# optodist_1_2_TH.net
KiCad netlist of a schematic drawn in EAGLE
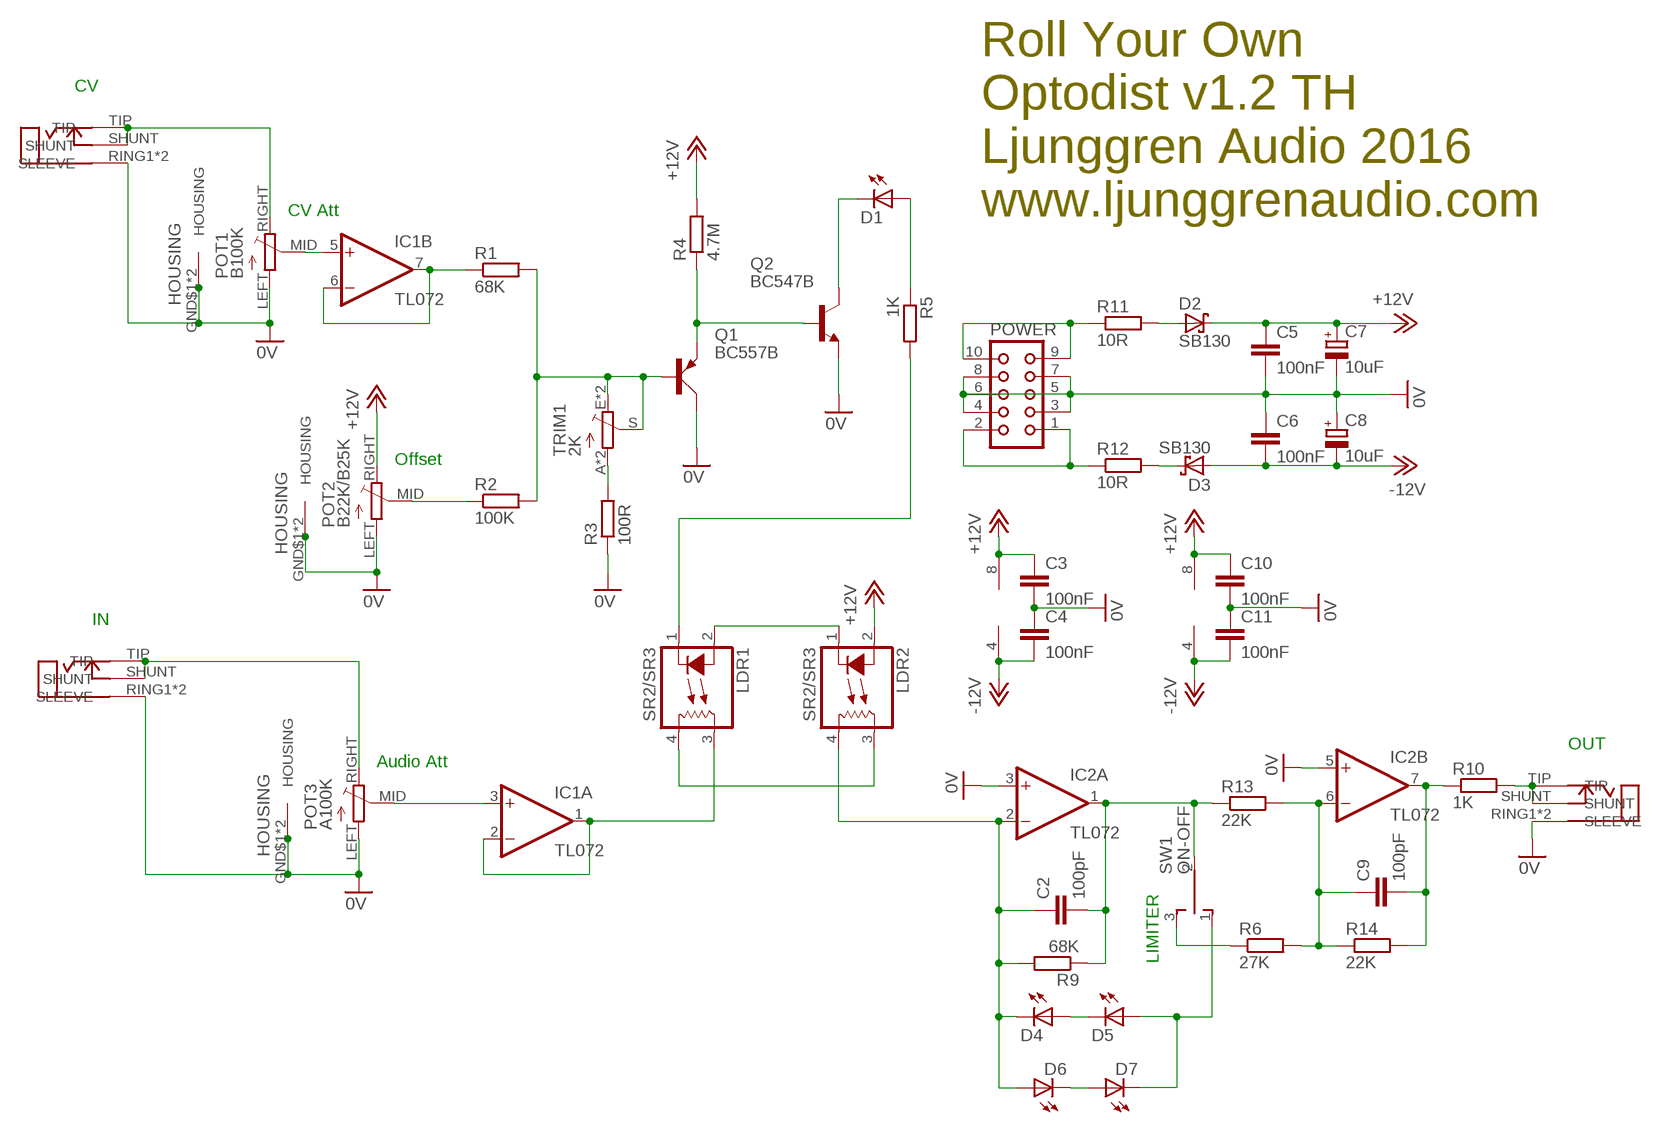
[diagram p0: schematic, sheet 1]

(export (version "E")
  (design (tool "Eeschema 10.0.6"))
  (components
    (comp (ref "C2")
      (value "100pF")
      (footprint "eagle-import:C025-024X044")
      (libsource (lib "eagle-import") (part "C-EU025-024X044"))
    )
    (comp (ref "C3")
      (value "100nF")
      (footprint "eagle-import:C025-024X044")
      (libsource (lib "eagle-import") (part "C-EU025-024X044"))
    )
    (comp (ref "C4")
      (value "100nF")
      (footprint "eagle-import:C025-024X044")
      (libsource (lib "eagle-import") (part "C-EU025-024X044"))
    )
    (comp (ref "C5")
      (value "100nF")
      (footprint "eagle-import:C025-024X044")
      (libsource (lib "eagle-import") (part "C-EU025-024X044"))
    )
    (comp (ref "C6")
      (value "100nF")
      (footprint "eagle-import:C025-024X044")
      (libsource (lib "eagle-import") (part "C-EU025-024X044"))
    )
    (comp (ref "C7")
      (value "10uF")
      (footprint "eagle-import:E2-5")
      (libsource (lib "eagle-import") (part "CPOL-EUE2-5"))
    )
    (comp (ref "C8")
      (value "10uF")
      (footprint "eagle-import:E2-5")
      (libsource (lib "eagle-import") (part "CPOL-EUE2-5"))
    )
    (comp (ref "C9")
      (value "100pF")
      (footprint "eagle-import:C025-024X044")
      (libsource (lib "eagle-import") (part "C-EU025-024X044"))
    )
    (comp (ref "C10")
      (value "100nF")
      (footprint "eagle-import:C025-024X044")
      (libsource (lib "eagle-import") (part "C-EU025-024X044"))
    )
    (comp (ref "C11")
      (value "100nF")
      (footprint "eagle-import:C025-024X044")
      (libsource (lib "eagle-import") (part "C-EU025-024X044"))
    )
    (comp (ref "CV")
      (value "ERTHENVAR_3.5MM_JACKHOLES")
      (footprint "eagle-import:ERTHENVAR")
      (libsource (lib "eagle-import") (part "ERTHENVAR_3.5MM_JACKHOLES"))
    )
    (comp (ref "D1")
      (value "LED3MM")
      (footprint "eagle-import:LED3MM")
      (libsource (lib "eagle-import") (part "LED3MM"))
    )
    (comp (ref "D2")
      (value "SB130")
      (footprint "eagle-import:DO41-7")
      (libsource (lib "eagle-import") (part "SB130DO-204AL"))
    )
    (comp (ref "D3")
      (value "SB130")
      (footprint "eagle-import:DO41-7")
      (libsource (lib "eagle-import") (part "SB130DO-204AL"))
    )
    (comp (ref "D4")
      (value "LED3MM")
      (footprint "eagle-import:LED3MM")
      (libsource (lib "eagle-import") (part "LED3MM"))
    )
    (comp (ref "D5")
      (value "LED3MM")
      (footprint "eagle-import:LED3MM")
      (libsource (lib "eagle-import") (part "LED3MM"))
    )
    (comp (ref "D6")
      (value "LED3MM")
      (footprint "eagle-import:LED3MM")
      (libsource (lib "eagle-import") (part "LED3MM"))
    )
    (comp (ref "D7")
      (value "LED3MM")
      (footprint "eagle-import:LED3MM")
      (libsource (lib "eagle-import") (part "LED3MM"))
    )
    (comp (ref "IC1")
      (value "TL072")
      (footprint "eagle-import:DIL08")
      (libsource (lib "eagle-import") (part "TL072P"))
    )
    (comp (ref "IC2")
      (value "TL072")
      (footprint "eagle-import:DIL08")
      (libsource (lib "eagle-import") (part "TL072P"))
    )
    (comp (ref "IN")
      (value "ERTHENVAR_3.5MM_JACKHOLES")
      (footprint "eagle-import:ERTHENVAR")
      (libsource (lib "eagle-import") (part "ERTHENVAR_3.5MM_JACKHOLES"))
    )
    (comp (ref "LDR1")
      (value "SR2/SR3")
      (footprint "eagle-import:VTL5C")
      (fields (field (name "MF") "VACTEC PHOTO") (field (name "MPN") "VTL5C9"))
      (libsource (lib "eagle-import") (part "VTL5CSILONEX9"))
    )
    (comp (ref "LDR2")
      (value "SR2/SR3")
      (footprint "eagle-import:VTL5C")
      (fields (field (name "MF") "VACTEC PHOTO") (field (name "MPN") "VTL5C9"))
      (libsource (lib "eagle-import") (part "VTL5CSILONEX9"))
    )
    (comp (ref "OUT")
      (value "ERTHENVAR_3.5MM_JACKHOLES")
      (footprint "eagle-import:ERTHENVAR")
      (libsource (lib "eagle-import") (part "ERTHENVAR_3.5MM_JACKHOLES"))
    )
    (comp (ref "POT1")
      (value "B100K")
      (footprint "eagle-import:POT-ALPHA9")
      (libsource (lib "eagle-import") (part "POT-ALPHA9"))
    )
    (comp (ref "POT2")
      (value "B22K/B25K")
      (footprint "eagle-import:POT-ALPHA9")
      (libsource (lib "eagle-import") (part "POT-ALPHA9"))
    )
    (comp (ref "POT3")
      (value "A100K")
      (footprint "eagle-import:POT-ALPHA9")
      (libsource (lib "eagle-import") (part "POT-ALPHA9"))
    )
    (comp (ref "POWER")
      (value "CON10L")
      (footprint "eagle-import:CON10L")
      (libsource (lib "eagle-import") (part "CON10L"))
    )
    (comp (ref "Q1")
      (value "BC557B")
      (footprint "eagle-import:TO92-LINE")
      (libsource (lib "eagle-import") (part "BC557TO92-LINE"))
    )
    (comp (ref "Q2")
      (value "BC547B")
      (footprint "eagle-import:TO92-LINE")
      (libsource (lib "eagle-import") (part "BC547TO92-LINE"))
    )
    (comp (ref "R1")
      (value "68K")
      (footprint "eagle-import:0207_9")
      (libsource (lib "eagle-import") (part "R-EU_0207/10"))
    )
    (comp (ref "R2")
      (value "100K")
      (footprint "eagle-import:0207_9")
      (libsource (lib "eagle-import") (part "R-EU_0207/10"))
    )
    (comp (ref "R3")
      (value "100R")
      (footprint "eagle-import:0207_9")
      (libsource (lib "eagle-import") (part "R-EU_0207/10"))
    )
    (comp (ref "R4")
      (value "4.7M")
      (footprint "eagle-import:0207_9")
      (libsource (lib "eagle-import") (part "R-EU_0207/10"))
    )
    (comp (ref "R5")
      (value "1K")
      (footprint "eagle-import:0207_9")
      (libsource (lib "eagle-import") (part "R-EU_0207/10"))
    )
    (comp (ref "R6")
      (value "27K")
      (footprint "eagle-import:0207_9")
      (libsource (lib "eagle-import") (part "R-EU_0207/10"))
    )
    (comp (ref "R9")
      (value "68K")
      (footprint "eagle-import:0207_9")
      (libsource (lib "eagle-import") (part "R-EU_0207/10"))
    )
    (comp (ref "R10")
      (value "1K")
      (footprint "eagle-import:0207_9")
      (libsource (lib "eagle-import") (part "R-EU_0207/10"))
    )
    (comp (ref "R11")
      (value "10R")
      (footprint "eagle-import:0207_9")
      (libsource (lib "eagle-import") (part "R-EU_0207/10"))
    )
    (comp (ref "R12")
      (value "10R")
      (footprint "eagle-import:0207_9")
      (libsource (lib "eagle-import") (part "R-EU_0207/10"))
    )
    (comp (ref "R13")
      (value "22K")
      (footprint "eagle-import:0207_9")
      (libsource (lib "eagle-import") (part "R-EU_0207/10"))
    )
    (comp (ref "R14")
      (value "22K")
      (footprint "eagle-import:0207_9")
      (libsource (lib "eagle-import") (part "R-EU_0207/10"))
    )
    (comp (ref "SW1")
      (value "ON-OFF")
      (footprint "eagle-import:SPDT-HORIZONTAL-TOP-SUBMINI-MULTICOMP")
      (libsource (lib "eagle-import") (part "SPDTTOP-SUBMINI"))
    )
    (comp (ref "TRIM1")
      (value "2K")
      (footprint "eagle-import:B25P")
      (libsource (lib "eagle-import") (part "TRIM_EU-B25P"))
    )
  )
  (nets
    (net (code "1") (name "+12V") (class "Default")
      (node (ref "C10") (pin "1") (pinfunction "1_1") (pintype "passive"))
      (node (ref "C3") (pin "1") (pinfunction "1_1") (pintype "passive"))
      (node (ref "C5") (pin "1") (pinfunction "1_1") (pintype "passive"))
      (node (ref "C7") (pin "+") (pinfunction "+_+") (pintype "passive"))
      (node (ref "D2") (pin "C") (pinfunction "C_C") (pintype "passive"))
      (node (ref "IC1") (pin "8") (pinfunction "V+_8") (pintype "power_in"))
      (node (ref "IC2") (pin "8") (pinfunction "V+_8") (pintype "power_in"))
      (node (ref "LDR2") (pin "2") (pinfunction "A_2") (pintype "passive"))
      (node (ref "POT2") (pin "RIGHT") (pinfunction "RIGHT_RIGHT") (pintype "passive"))
      (node (ref "R4") (pin "2") (pinfunction "2_2") (pintype "passive"))
    )
    (net (code "2") (name "-12V") (class "Default")
      (node (ref "C11") (pin "2") (pinfunction "2_2") (pintype "passive"))
      (node (ref "C4") (pin "2") (pinfunction "2_2") (pintype "passive"))
      (node (ref "C6") (pin "2") (pinfunction "2_2") (pintype "passive"))
      (node (ref "C8") (pin "-") (pinfunction "-_-") (pintype "passive"))
      (node (ref "D3") (pin "A") (pinfunction "A_A") (pintype "passive"))
      (node (ref "IC1") (pin "4") (pinfunction "V-_4") (pintype "power_in"))
      (node (ref "IC2") (pin "4") (pinfunction "V-_4") (pintype "power_in"))
    )
    (net (code "3") (name "0V") (class "Default")
      (node (ref "C10") (pin "2") (pinfunction "2_2") (pintype "passive"))
      (node (ref "C11") (pin "1") (pinfunction "1_1") (pintype "passive"))
      (node (ref "C3") (pin "2") (pinfunction "2_2") (pintype "passive"))
      (node (ref "C4") (pin "1") (pinfunction "1_1") (pintype "passive"))
      (node (ref "C5") (pin "2") (pinfunction "2_2") (pintype "passive"))
      (node (ref "C6") (pin "1") (pinfunction "1_1") (pintype "passive"))
      (node (ref "C7") (pin "-") (pinfunction "-_-") (pintype "passive"))
      (node (ref "C8") (pin "+") (pinfunction "+_+") (pintype "passive"))
      (node (ref "CV") (pin "RING1") (pinfunction "SLEEVE_RING1") (pintype "bidirectional"))
      (node (ref "CV") (pin "RING2") (pinfunction "SLEEVE_RING2") (pintype "bidirectional"))
      (node (ref "IC2") (pin "3") (pinfunction "+IN_3") (pintype "input"))
      (node (ref "IC2") (pin "5") (pinfunction "+IN_5") (pintype "input"))
      (node (ref "IN") (pin "RING1") (pinfunction "SLEEVE_RING1") (pintype "bidirectional"))
      (node (ref "IN") (pin "RING2") (pinfunction "SLEEVE_RING2") (pintype "bidirectional"))
      (node (ref "OUT") (pin "RING1") (pinfunction "SLEEVE_RING1") (pintype "bidirectional"))
      (node (ref "OUT") (pin "RING2") (pinfunction "SLEEVE_RING2") (pintype "bidirectional"))
      (node (ref "POT1") (pin "GND$1") (pinfunction "HOUSING_GND$1") (pintype "bidirectional"))
      (node (ref "POT1") (pin "GND$2") (pinfunction "HOUSING_GND$2") (pintype "bidirectional"))
      (node (ref "POT1") (pin "LEFT") (pinfunction "LEFT_LEFT") (pintype "passive"))
      (node (ref "POT2") (pin "GND$1") (pinfunction "HOUSING_GND$1") (pintype "bidirectional"))
      (node (ref "POT2") (pin "GND$2") (pinfunction "HOUSING_GND$2") (pintype "bidirectional"))
      (node (ref "POT2") (pin "LEFT") (pinfunction "LEFT_LEFT") (pintype "passive"))
      (node (ref "POT3") (pin "GND$1") (pinfunction "HOUSING_GND$1") (pintype "bidirectional"))
      (node (ref "POT3") (pin "GND$2") (pinfunction "HOUSING_GND$2") (pintype "bidirectional"))
      (node (ref "POT3") (pin "LEFT") (pinfunction "LEFT_LEFT") (pintype "passive"))
      (node (ref "POWER") (pin "3") (pinfunction "3_3") (pintype "passive"))
      (node (ref "POWER") (pin "4") (pinfunction "4_4") (pintype "passive"))
      (node (ref "POWER") (pin "5") (pinfunction "5_5") (pintype "passive"))
      (node (ref "POWER") (pin "6") (pinfunction "6_6") (pintype "passive"))
      (node (ref "POWER") (pin "7") (pinfunction "7_7") (pintype "passive"))
      (node (ref "POWER") (pin "8") (pinfunction "8_8") (pintype "passive"))
      (node (ref "Q1") (pin "3") (pinfunction "C_3") (pintype "passive"))
      (node (ref "Q2") (pin "1") (pinfunction "E_1") (pintype "passive"))
      (node (ref "R3") (pin "1") (pinfunction "1_1") (pintype "passive"))
    )
    (net (code "4") (name "Net-(CV-PadSHUNT)") (class "Default")
      (node (ref "CV") (pin "SHUNT") (pinfunction "SHUNT_SHUNT") (pintype "bidirectional"))
      (node (ref "CV") (pin "TIP") (pinfunction "TIP_TIP") (pintype "bidirectional"))
      (node (ref "POT1") (pin "RIGHT") (pinfunction "RIGHT_RIGHT") (pintype "passive"))
    )
    (net (code "5") (name "Net-(D1-C)") (class "Default")
      (node (ref "D1") (pin "K") (pinfunction "C_K") (pintype "passive"))
      (node (ref "Q2") (pin "3") (pinfunction "C_3") (pintype "passive"))
    )
    (net (code "6") (name "Net-(D1-PadA)") (class "Default")
      (node (ref "D1") (pin "A") (pinfunction "A_A") (pintype "passive"))
      (node (ref "R5") (pin "1") (pinfunction "1_1") (pintype "passive"))
    )
    (net (code "7") (name "Net-(D2-PadA)") (class "Default")
      (node (ref "D2") (pin "A") (pinfunction "A_A") (pintype "passive"))
      (node (ref "R11") (pin "2") (pinfunction "2_2") (pintype "passive"))
    )
    (net (code "8") (name "Net-(D3-PadC)") (class "Default")
      (node (ref "D3") (pin "C") (pinfunction "C_C") (pintype "passive"))
      (node (ref "R12") (pin "2") (pinfunction "2_2") (pintype "passive"))
    )
    (net (code "9") (name "Net-(D4-C)") (class "Default")
      (node (ref "C2") (pin "1") (pinfunction "1_1") (pintype "passive"))
      (node (ref "D4") (pin "K") (pinfunction "C_K") (pintype "passive"))
      (node (ref "D6") (pin "A") (pinfunction "A_A") (pintype "passive"))
      (node (ref "IC2") (pin "2") (pinfunction "-IN_2") (pintype "input"))
      (node (ref "LDR2") (pin "4") (pinfunction "L2_4") (pintype "passive"))
      (node (ref "R9") (pin "2") (pinfunction "2_2") (pintype "passive"))
    )
    (net (code "10") (name "Net-(D5-C)") (class "Default")
      (node (ref "D4") (pin "A") (pinfunction "A_A") (pintype "passive"))
      (node (ref "D5") (pin "K") (pinfunction "C_K") (pintype "passive"))
    )
    (net (code "11") (name "Net-(D6-C)") (class "Default")
      (node (ref "D6") (pin "K") (pinfunction "C_K") (pintype "passive"))
      (node (ref "D7") (pin "A") (pinfunction "A_A") (pintype "passive"))
    )
    (net (code "12") (name "Net-(D7-C)") (class "Default")
      (node (ref "D5") (pin "A") (pinfunction "A_A") (pintype "passive"))
      (node (ref "D7") (pin "K") (pinfunction "C_K") (pintype "passive"))
      (node (ref "SW1") (pin "1") (pinfunction "1_1") (pintype "passive"))
    )
    (net (code "13") (name "Net-(IC1A-+IN)") (class "Default")
      (node (ref "IC1") (pin "3") (pinfunction "+IN_3") (pintype "input"))
      (node (ref "POT3") (pin "MID") (pinfunction "MID_MID") (pintype "passive"))
    )
    (net (code "14") (name "Net-(IC1A--IN)") (class "Default")
      (node (ref "IC1") (pin "1") (pinfunction "OUT_1") (pintype "output"))
      (node (ref "IC1") (pin "2") (pinfunction "-IN_2") (pintype "input"))
      (node (ref "LDR1") (pin "3") (pinfunction "L1_3") (pintype "passive"))
    )
    (net (code "15") (name "Net-(IC1B-+IN)") (class "Default")
      (node (ref "IC1") (pin "5") (pinfunction "+IN_5") (pintype "input"))
      (node (ref "POT1") (pin "MID") (pinfunction "MID_MID") (pintype "passive"))
    )
    (net (code "16") (name "Net-(IC1B--IN)") (class "Default")
      (node (ref "IC1") (pin "6") (pinfunction "-IN_6") (pintype "input"))
      (node (ref "IC1") (pin "7") (pinfunction "OUT_7") (pintype "output"))
      (node (ref "R1") (pin "1") (pinfunction "1_1") (pintype "passive"))
    )
    (net (code "17") (name "Net-(IC2A-OUT)") (class "Default")
      (node (ref "C2") (pin "2") (pinfunction "2_2") (pintype "passive"))
      (node (ref "IC2") (pin "1") (pinfunction "OUT_1") (pintype "output"))
      (node (ref "R13") (pin "1") (pinfunction "1_1") (pintype "passive"))
      (node (ref "R9") (pin "1") (pinfunction "1_1") (pintype "passive"))
      (node (ref "SW1") (pin "2") (pinfunction "2_2") (pintype "passive"))
    )
    (net (code "18") (name "Net-(IC2B--IN)") (class "Default")
      (node (ref "C9") (pin "1") (pinfunction "1_1") (pintype "passive"))
      (node (ref "IC2") (pin "6") (pinfunction "-IN_6") (pintype "input"))
      (node (ref "R13") (pin "2") (pinfunction "2_2") (pintype "passive"))
      (node (ref "R14") (pin "1") (pinfunction "1_1") (pintype "passive"))
      (node (ref "R6") (pin "2") (pinfunction "2_2") (pintype "passive"))
    )
    (net (code "19") (name "Net-(IC2B-OUT)") (class "Default")
      (node (ref "C9") (pin "2") (pinfunction "2_2") (pintype "passive"))
      (node (ref "IC2") (pin "7") (pinfunction "OUT_7") (pintype "output"))
      (node (ref "R10") (pin "1") (pinfunction "1_1") (pintype "passive"))
      (node (ref "R14") (pin "2") (pinfunction "2_2") (pintype "passive"))
    )
    (net (code "20") (name "Net-(IN-PadSHUNT)") (class "Default")
      (node (ref "IN") (pin "SHUNT") (pinfunction "SHUNT_SHUNT") (pintype "bidirectional"))
      (node (ref "IN") (pin "TIP") (pinfunction "TIP_TIP") (pintype "bidirectional"))
      (node (ref "POT3") (pin "RIGHT") (pinfunction "RIGHT_RIGHT") (pintype "passive"))
    )
    (net (code "21") (name "Net-(LDR1-A)") (class "Default")
      (node (ref "LDR1") (pin "2") (pinfunction "A_2") (pintype "passive"))
      (node (ref "LDR2") (pin "1") (pinfunction "C_1") (pintype "passive"))
    )
    (net (code "22") (name "Net-(LDR1-C)") (class "Default")
      (node (ref "LDR1") (pin "1") (pinfunction "C_1") (pintype "passive"))
      (node (ref "R5") (pin "2") (pinfunction "2_2") (pintype "passive"))
    )
    (net (code "23") (name "Net-(LDR1-L2)") (class "Default")
      (node (ref "LDR1") (pin "4") (pinfunction "L2_4") (pintype "passive"))
      (node (ref "LDR2") (pin "3") (pinfunction "L1_3") (pintype "passive"))
    )
    (net (code "24") (name "Net-(OUT-PadSHUNT)") (class "Default")
      (node (ref "OUT") (pin "SHUNT") (pinfunction "SHUNT_SHUNT") (pintype "bidirectional"))
      (node (ref "OUT") (pin "TIP") (pinfunction "TIP_TIP") (pintype "bidirectional"))
      (node (ref "R10") (pin "2") (pinfunction "2_2") (pintype "passive"))
    )
    (net (code "25") (name "Net-(POT2-PadMID)") (class "Default")
      (node (ref "POT2") (pin "MID") (pinfunction "MID_MID") (pintype "passive"))
      (node (ref "R2") (pin "1") (pinfunction "1_1") (pintype "passive"))
    )
    (net (code "26") (name "Net-(POWER-Pad1)") (class "Default")
      (node (ref "POWER") (pin "1") (pinfunction "1_1") (pintype "passive"))
      (node (ref "POWER") (pin "2") (pinfunction "2_2") (pintype "passive"))
      (node (ref "R12") (pin "1") (pinfunction "1_1") (pintype "passive"))
    )
    (net (code "27") (name "Net-(POWER-Pad10)") (class "Default")
      (node (ref "POWER") (pin "10") (pinfunction "10_10") (pintype "passive"))
      (node (ref "POWER") (pin "9") (pinfunction "9_9") (pintype "passive"))
      (node (ref "R11") (pin "1") (pinfunction "1_1") (pintype "passive"))
    )
    (net (code "28") (name "Net-(Q1-B)") (class "Default")
      (node (ref "Q1") (pin "2") (pinfunction "B_2") (pintype "passive"))
      (node (ref "R1") (pin "2") (pinfunction "2_2") (pintype "passive"))
      (node (ref "R2") (pin "2") (pinfunction "2_2") (pintype "passive"))
      (node (ref "TRIM1") (pin "E") (pinfunction "E_E") (pintype "passive"))
      (node (ref "TRIM1") (pin "EE") (pinfunction "E_EE") (pintype "passive"))
      (node (ref "TRIM1") (pin "S") (pinfunction "S_S") (pintype "passive"))
    )
    (net (code "29") (name "Net-(Q1-E)") (class "Default")
      (node (ref "Q1") (pin "1") (pinfunction "E_1") (pintype "passive"))
      (node (ref "Q2") (pin "2") (pinfunction "B_2") (pintype "passive"))
      (node (ref "R4") (pin "1") (pinfunction "1_1") (pintype "passive"))
    )
    (net (code "30") (name "Net-(R3-Pad2)") (class "Default")
      (node (ref "R3") (pin "2") (pinfunction "2_2") (pintype "passive"))
      (node (ref "TRIM1") (pin "A") (pinfunction "A_A") (pintype "passive"))
      (node (ref "TRIM1") (pin "AA") (pinfunction "A_AA") (pintype "passive"))
    )
    (net (code "31") (name "Net-(R6-Pad1)") (class "Default")
      (node (ref "R6") (pin "1") (pinfunction "1_1") (pintype "passive"))
      (node (ref "SW1") (pin "3") (pinfunction "3_3") (pintype "passive"))
    )
  )
)
